# SCH-10-Power_Connectors.net
KiCad netlist of a schematic drawn in Altium Designer
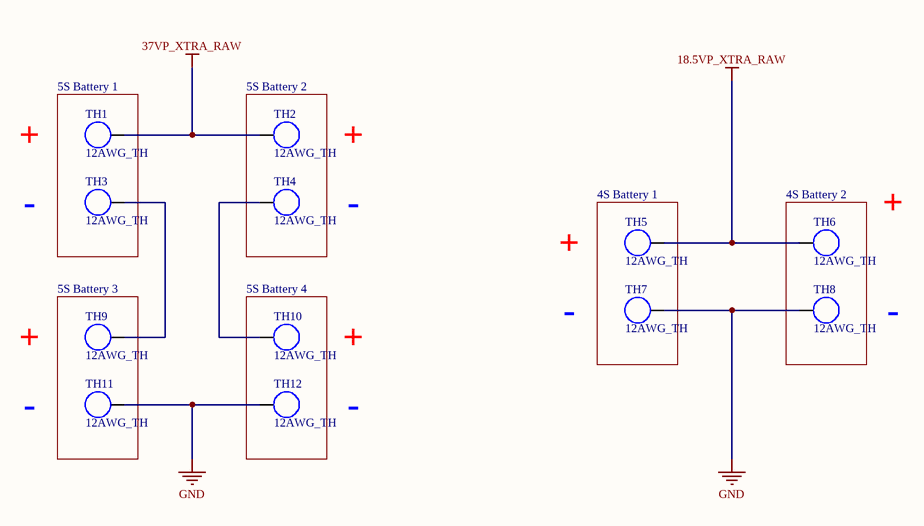
[diagram p0: SCH-10-Power Connectors.SchDoc]

(export (version "E")
  (design (tool "Eeschema 10.0.6"))
  (components
    (comp (ref "TH1")
      (value "12AWG_TH")
      (footprint "12AWG_Wire_TH")
      (libsource (lib "RSX_Mechanicals") (part "12AWG_TH"))
    )
    (comp (ref "TH2")
      (value "12AWG_TH")
      (footprint "12AWG_Wire_TH")
      (libsource (lib "RSX_Mechanicals") (part "12AWG_TH"))
    )
    (comp (ref "TH3")
      (value "12AWG_TH")
      (footprint "12AWG_Wire_TH")
      (libsource (lib "RSX_Mechanicals") (part "12AWG_TH"))
    )
    (comp (ref "TH4")
      (value "12AWG_TH")
      (footprint "12AWG_Wire_TH")
      (libsource (lib "RSX_Mechanicals") (part "12AWG_TH"))
    )
    (comp (ref "TH5")
      (value "12AWG_TH")
      (footprint "12AWG_Wire_TH")
      (libsource (lib "RSX_Mechanicals") (part "12AWG_TH"))
    )
    (comp (ref "TH6")
      (value "12AWG_TH")
      (footprint "12AWG_Wire_TH")
      (libsource (lib "RSX_Mechanicals") (part "12AWG_TH"))
    )
    (comp (ref "TH7")
      (value "12AWG_TH")
      (footprint "12AWG_Wire_TH")
      (libsource (lib "RSX_Mechanicals") (part "12AWG_TH"))
    )
    (comp (ref "TH8")
      (value "12AWG_TH")
      (footprint "12AWG_Wire_TH")
      (libsource (lib "RSX_Mechanicals") (part "12AWG_TH"))
    )
    (comp (ref "TH9")
      (value "12AWG_TH")
      (footprint "12AWG_Wire_TH")
      (libsource (lib "RSX_Mechanicals") (part "12AWG_TH"))
    )
    (comp (ref "TH10")
      (value "12AWG_TH")
      (footprint "12AWG_Wire_TH")
      (libsource (lib "RSX_Mechanicals") (part "12AWG_TH"))
    )
    (comp (ref "TH11")
      (value "12AWG_TH")
      (footprint "12AWG_Wire_TH")
      (libsource (lib "RSX_Mechanicals") (part "12AWG_TH"))
    )
    (comp (ref "TH12")
      (value "12AWG_TH")
      (footprint "12AWG_Wire_TH")
      (libsource (lib "RSX_Mechanicals") (part "12AWG_TH"))
    )
  )
  (nets
    (net (code "1") (name "18.5VP_XTRA_RAW") (class "Default")
      (node (ref "TH5") (pin "1") (pinfunction "1_1") (pintype "passive"))
      (node (ref "TH6") (pin "1") (pinfunction "1_1") (pintype "passive"))
    )
    (net (code "2") (name "37VP_XTRA_RAW") (class "Default")
      (node (ref "TH1") (pin "1") (pinfunction "1_1") (pintype "passive"))
      (node (ref "TH2") (pin "1") (pinfunction "1_1") (pintype "passive"))
    )
    (net (code "3") (name "GND") (class "Default")
      (node (ref "TH11") (pin "1") (pinfunction "1_1") (pintype "passive"))
      (node (ref "TH12") (pin "1") (pinfunction "1_1") (pintype "passive"))
      (node (ref "TH7") (pin "1") (pinfunction "1_1") (pintype "passive"))
      (node (ref "TH8") (pin "1") (pinfunction "1_1") (pintype "passive"))
    )
    (net (code "4") (name "Net-(TH3-Pad1)") (class "Default")
      (node (ref "TH3") (pin "1") (pinfunction "1_1") (pintype "passive"))
      (node (ref "TH9") (pin "1") (pinfunction "1_1") (pintype "passive"))
    )
    (net (code "5") (name "Net-(TH10-Pad1)") (class "Default")
      (node (ref "TH10") (pin "1") (pinfunction "1_1") (pintype "passive"))
      (node (ref "TH4") (pin "1") (pinfunction "1_1") (pintype "passive"))
    )
  )
)
